# ESP32-Wrover-DevBoard.net
KiCad netlist of a schematic drawn in EAGLE
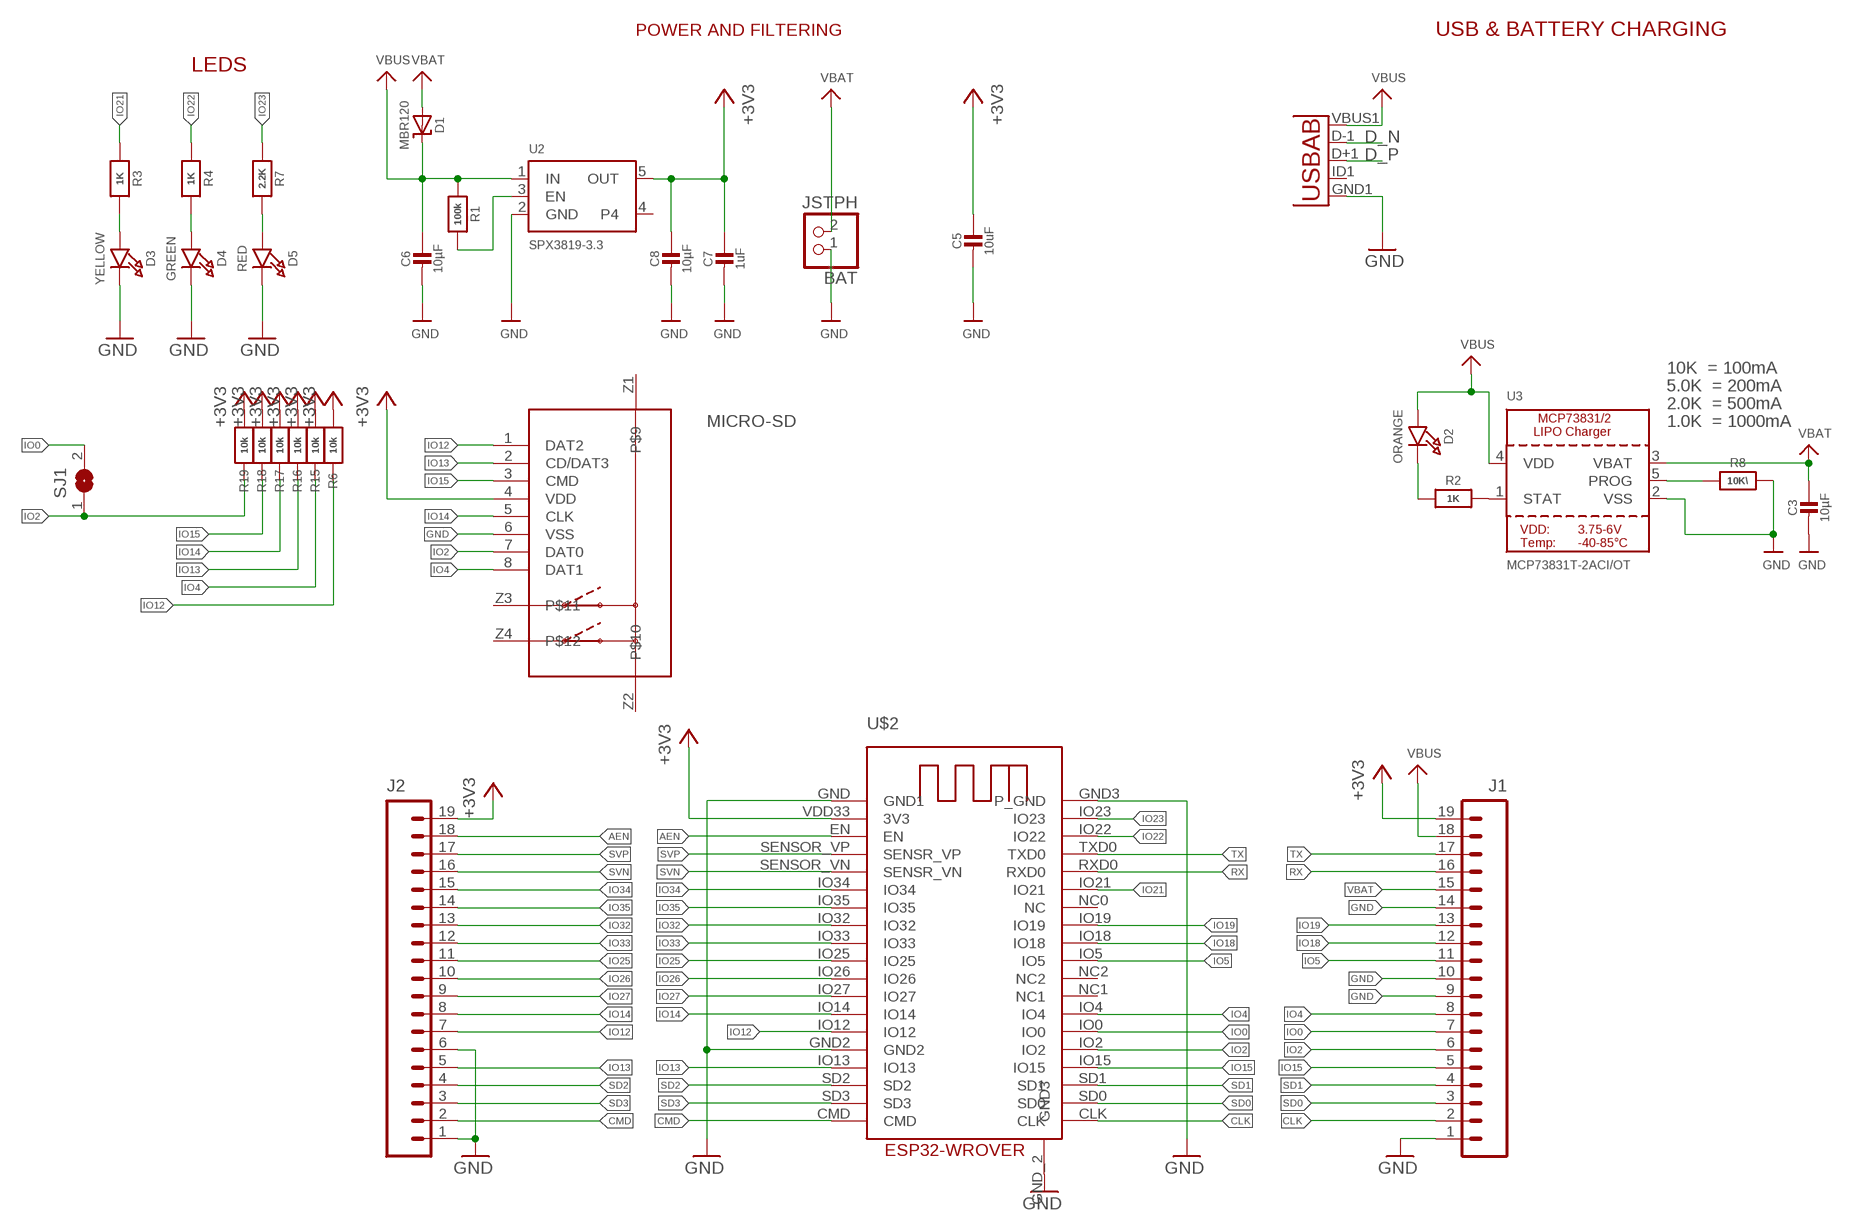
[diagram p0: schematic, sheet 1, part 1 of 2]
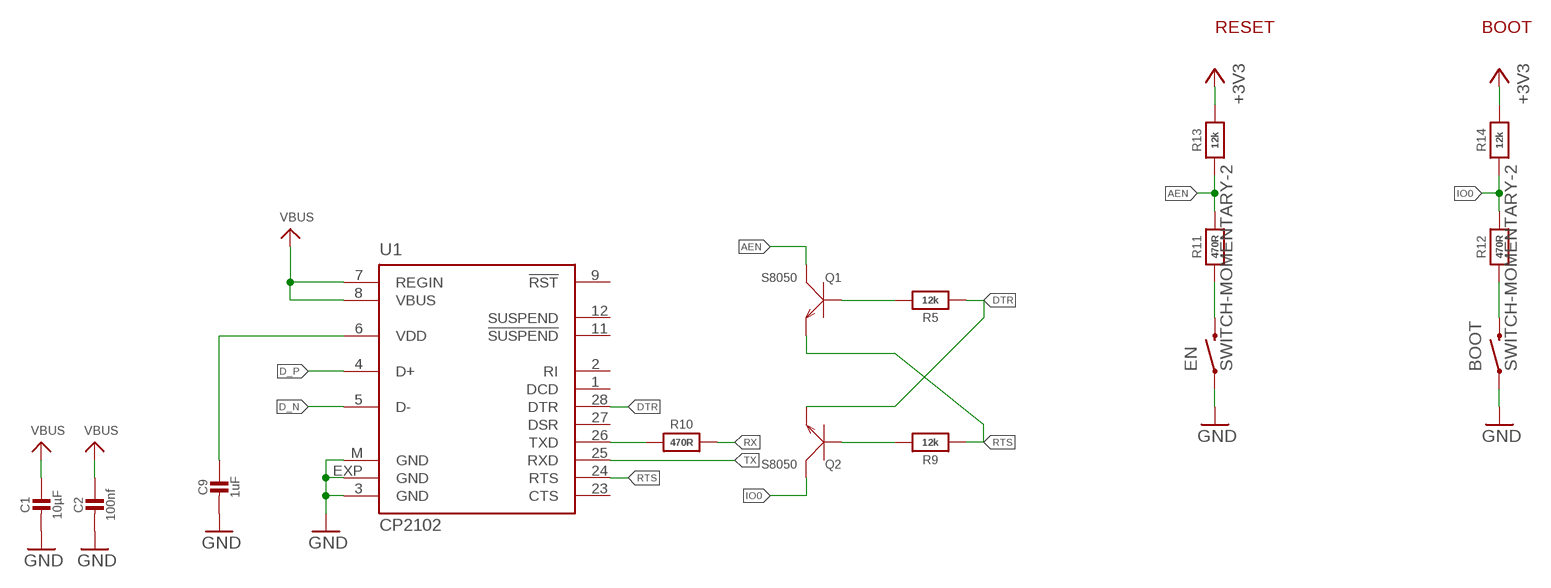
[diagram p1: schematic, sheet 1, part 2 of 2]

(export (version "E")
  (design (tool "Eeschema 10.0.6"))
  (components
    (comp (ref "BAT")
      (value "JSTPH")
      (footprint "eagle-import:JSTPH2")
      (libsource (lib "eagle-import") (part "CON_JST_PH_2PIN"))
    )
    (comp (ref "BOOT")
      (value "SWITCH-MOMENTARY-2")
      (footprint "eagle-import:WS-TRS-6.0X3.5MM-TACT-SWITCH_SMD")
      (libsource (lib "eagle-import") (part "SWITCH-MOMENTARY-2"))
    )
    (comp (ref "C1")
      (value "10µF")
      (footprint "eagle-import:0805-NO")
      (libsource (lib "eagle-import") (part "CAP_CERAMIC0805-NOOUTLINE"))
    )
    (comp (ref "C2")
      (value "100nf")
      (footprint "eagle-import:0603-NO")
      (libsource (lib "eagle-import") (part "CAP_CERAMIC0603_NO"))
    )
    (comp (ref "C3")
      (value "10µF")
      (footprint "eagle-import:0805-NO")
      (libsource (lib "eagle-import") (part "CAP_CERAMIC0805-NOOUTLINE"))
    )
    (comp (ref "C5")
      (value "10uF")
      (footprint "eagle-import:0805-NO")
      (libsource (lib "eagle-import") (part "CAP_CERAMIC0805-NOOUTLINE"))
    )
    (comp (ref "C6")
      (value "10µF")
      (footprint "eagle-import:0805-NO")
      (libsource (lib "eagle-import") (part "CAP_CERAMIC0805-NOOUTLINE"))
    )
    (comp (ref "C7")
      (value "1uF")
      (footprint "eagle-import:0603-NO")
      (libsource (lib "eagle-import") (part "CAP_CERAMIC0603_NO"))
    )
    (comp (ref "C8")
      (value "10µF")
      (footprint "eagle-import:0805-NO")
      (libsource (lib "eagle-import") (part "CAP_CERAMIC0805-NOOUTLINE"))
    )
    (comp (ref "C9")
      (value "1uF")
      (footprint "eagle-import:0603-NO")
      (libsource (lib "eagle-import") (part "CAP_CERAMIC0603_NO"))
    )
    (comp (ref "D1")
      (value "MBR120")
      (footprint "eagle-import:SOD-123")
      (libsource (lib "eagle-import") (part "DIODE-SCHOTTKYSOD-123"))
    )
    (comp (ref "D2")
      (value "ORANGE")
      (footprint "eagle-import:CHIPLED_0805_NOOUTLINE")
      (libsource (lib "eagle-import") (part "LED0805_NOOUTLINE"))
    )
    (comp (ref "D3")
      (value "YELLOW")
      (footprint "eagle-import:CHIPLED_0805_NOOUTLINE")
      (libsource (lib "eagle-import") (part "LED0805_NOOUTLINE"))
    )
    (comp (ref "D4")
      (value "GREEN")
      (footprint "eagle-import:CHIPLED_0805_NOOUTLINE")
      (libsource (lib "eagle-import") (part "LED0805_NOOUTLINE"))
    )
    (comp (ref "D5")
      (value "RED")
      (footprint "eagle-import:CHIPLED_0805_NOOUTLINE")
      (libsource (lib "eagle-import") (part "LED0805_NOOUTLINE"))
    )
    (comp (ref "EN")
      (value "SWITCH-MOMENTARY-2")
      (footprint "eagle-import:WS-TRS-6.0X3.5MM-TACT-SWITCH_SMD")
      (libsource (lib "eagle-import") (part "SWITCH-MOMENTARY-2"))
    )
    (comp (ref "J1")
      (value "M191X19_NO_SILK")
      (footprint "eagle-import:1X19_NO_SILK")
      (libsource (lib "eagle-import") (part "M191X19_NO_SILK"))
    )
    (comp (ref "J2")
      (value "M191X19_NO_SILK")
      (footprint "eagle-import:1X19_NO_SILK")
      (libsource (lib "eagle-import") (part "M191X19_NO_SILK"))
    )
    (comp (ref "M-USB")
      (value "USB\"\"")
      (footprint "eagle-import:USB-MICRO-SMD")
      (libsource (lib "eagle-import") (part "USB{dblquote}{dblquote}"))
    )
    (comp (ref "MICRO-SD")
      (value "693072010801")
      (footprint "eagle-import:693072010801")
      (libsource (lib "eagle-import") (part "693072010801"))
    )
    (comp (ref "Q1")
      (value "S8050")
      (footprint "eagle-import:SOT-23")
      (libsource (lib "eagle-import") (part "SMD-TRANSISTORS-NPN-25V-500MW-S8050(SOT-23)"))
    )
    (comp (ref "Q2")
      (value "S8050")
      (footprint "eagle-import:SOT-23")
      (libsource (lib "eagle-import") (part "SMD-TRANSISTORS-NPN-25V-500MW-S8050(SOT-23)"))
    )
    (comp (ref "R1")
      (value "100k")
      (footprint "eagle-import:0603-NO")
      (libsource (lib "eagle-import") (part "RESISTOR_0603_NOOUT"))
    )
    (comp (ref "R2")
      (value "1K")
      (footprint "eagle-import:0603-NO")
      (libsource (lib "eagle-import") (part "RESISTOR_0603_NOOUT"))
    )
    (comp (ref "R3")
      (value "1K")
      (footprint "eagle-import:0603-NO")
      (libsource (lib "eagle-import") (part "RESISTOR_0603_NOOUT"))
    )
    (comp (ref "R4")
      (value "1K")
      (footprint "eagle-import:0603-NO")
      (libsource (lib "eagle-import") (part "RESISTOR_0603_NOOUT"))
    )
    (comp (ref "R5")
      (value "12k")
      (footprint "eagle-import:0603-NO")
      (libsource (lib "eagle-import") (part "RESISTOR_0603_NOOUT"))
    )
    (comp (ref "R6")
      (value "10k")
      (footprint "eagle-import:0603-NO")
      (libsource (lib "eagle-import") (part "RESISTOR_0603_NOOUT"))
    )
    (comp (ref "R7")
      (value "2.2K")
      (footprint "eagle-import:0603-NO")
      (libsource (lib "eagle-import") (part "RESISTOR_0603_NOOUT"))
    )
    (comp (ref "R8")
      (value "10K\\")
      (footprint "eagle-import:0603-NO")
      (libsource (lib "eagle-import") (part "RESISTOR_0603_NOOUT"))
    )
    (comp (ref "R9")
      (value "12k")
      (footprint "eagle-import:0603-NO")
      (libsource (lib "eagle-import") (part "RESISTOR_0603_NOOUT"))
    )
    (comp (ref "R10")
      (value "470R")
      (footprint "eagle-import:0603-NO")
      (libsource (lib "eagle-import") (part "RESISTOR_0603_NOOUT"))
    )
    (comp (ref "R11")
      (value "470R")
      (footprint "eagle-import:0603-NO")
      (libsource (lib "eagle-import") (part "RESISTOR_0603_NOOUT"))
    )
    (comp (ref "R12")
      (value "470R")
      (footprint "eagle-import:0603-NO")
      (libsource (lib "eagle-import") (part "RESISTOR_0603_NOOUT"))
    )
    (comp (ref "R13")
      (value "12k")
      (footprint "eagle-import:0603-NO")
      (libsource (lib "eagle-import") (part "RESISTOR_0603_NOOUT"))
    )
    (comp (ref "R14")
      (value "12k")
      (footprint "eagle-import:0603-NO")
      (libsource (lib "eagle-import") (part "RESISTOR_0603_NOOUT"))
    )
    (comp (ref "R15")
      (value "10k")
      (footprint "eagle-import:0603-NO")
      (libsource (lib "eagle-import") (part "RESISTOR_0603_NOOUT"))
    )
    (comp (ref "R16")
      (value "10k")
      (footprint "eagle-import:0603-NO")
      (libsource (lib "eagle-import") (part "RESISTOR_0603_NOOUT"))
    )
    (comp (ref "R17")
      (value "10k")
      (footprint "eagle-import:0603-NO")
      (libsource (lib "eagle-import") (part "RESISTOR_0603_NOOUT"))
    )
    (comp (ref "R18")
      (value "10k")
      (footprint "eagle-import:0603-NO")
      (libsource (lib "eagle-import") (part "RESISTOR_0603_NOOUT"))
    )
    (comp (ref "R19")
      (value "10k")
      (footprint "eagle-import:0603-NO")
      (libsource (lib "eagle-import") (part "RESISTOR_0603_NOOUT"))
    )
    (comp (ref "SJ1") (value "SJ") (footprint "eagle-import:SJ") (libsource (lib "eagle-import") (part "SJ")))
    (comp (ref "U$2")
      (value "ESP32-WROVER")
      (footprint "eagle-import:ESP32-WROVER")
      (libsource (lib "eagle-import") (part "ESP32-WROVER"))
    )
    (comp (ref "U1")
      (value "CP2102")
      (footprint "eagle-import:MLP28")
      (fields (field (name "MF") "FARNELL") (field (name "MPN") "CP2102-GM"))
      (libsource (lib "eagle-import") (part "CP2102"))
    )
    (comp (ref "U2")
      (value "SPX3819-3.3")
      (footprint "eagle-import:SOT23-5")
      (libsource (lib "eagle-import") (part "VREG_SOT23-5"))
    )
    (comp (ref "U3")
      (value "MCP73831T-2ACI/OT")
      (footprint "eagle-import:SOT23-5")
      (libsource (lib "eagle-import") (part "MCP73831/2"))
    )
  )
  (nets
    (net (code "1") (name "+3V3") (class "Default")
      (node (ref "C5") (pin "1") (pinfunction "1_1") (pintype "passive"))
      (node (ref "C7") (pin "1") (pinfunction "1_1") (pintype "passive"))
      (node (ref "C8") (pin "1") (pinfunction "1_1") (pintype "passive"))
      (node (ref "J1") (pin "19") (pinfunction "19_19") (pintype "passive"))
      (node (ref "J2") (pin "19") (pinfunction "19_19") (pintype "passive"))
      (node (ref "MICRO-SD") (pin "4") (pinfunction "VDD_4") (pintype "bidirectional"))
      (node (ref "R13") (pin "2") (pinfunction "2_2") (pintype "passive"))
      (node (ref "R14") (pin "2") (pinfunction "2_2") (pintype "passive"))
      (node (ref "R15") (pin "1") (pinfunction "1_1") (pintype "passive"))
      (node (ref "R16") (pin "1") (pinfunction "1_1") (pintype "passive"))
      (node (ref "R17") (pin "1") (pinfunction "1_1") (pintype "passive"))
      (node (ref "R18") (pin "1") (pinfunction "1_1") (pintype "passive"))
      (node (ref "R19") (pin "1") (pinfunction "1_1") (pintype "passive"))
      (node (ref "R6") (pin "1") (pinfunction "1_1") (pintype "passive"))
      (node (ref "U$2") (pin "VDD33") (pinfunction "3V3_VDD33") (pintype "bidirectional"))
      (node (ref "U2") (pin "5") (pinfunction "OUT_5") (pintype "power_in"))
    )
    (net (code "2") (name "AEN") (class "Default")
      (node (ref "J2") (pin "18") (pinfunction "18_18") (pintype "passive"))
      (node (ref "Q1") (pin "3") (pinfunction "C_3") (pintype "passive"))
      (node (ref "R11") (pin "2") (pinfunction "2_2") (pintype "passive"))
      (node (ref "R13") (pin "1") (pinfunction "1_1") (pintype "passive"))
      (node (ref "U$2") (pin "EN") (pinfunction "EN_EN") (pintype "bidirectional"))
    )
    (net (code "3") (name "CLK") (class "Default")
      (node (ref "J1") (pin "2") (pinfunction "2_2") (pintype "passive"))
      (node (ref "U$2") (pin "CLK") (pinfunction "CLK_CLK") (pintype "bidirectional"))
    )
    (net (code "4") (name "CMD") (class "Default")
      (node (ref "J2") (pin "2") (pinfunction "2_2") (pintype "passive"))
      (node (ref "U$2") (pin "CMD") (pinfunction "CMD_CMD") (pintype "bidirectional"))
    )
    (net (code "5") (name "DTR") (class "Default")
      (node (ref "Q2") (pin "2") (pinfunction "E_2") (pintype "passive"))
      (node (ref "R5") (pin "1") (pinfunction "1_1") (pintype "passive"))
      (node (ref "U1") (pin "28") (pinfunction "DTR_28") (pintype "output"))
    )
    (net (code "6") (name "D_N") (class "Default")
      (node (ref "M-USB") (pin "D-1") (pinfunction "D-_D-1") (pintype "bidirectional"))
      (node (ref "U1") (pin "5") (pinfunction "D-_5") (pintype "bidirectional"))
    )
    (net (code "7") (name "D_P") (class "Default")
      (node (ref "M-USB") (pin "D+1") (pinfunction "D+_D+1") (pintype "bidirectional"))
      (node (ref "U1") (pin "4") (pinfunction "D+_4") (pintype "bidirectional"))
    )
    (net (code "8") (name "GND") (class "Default")
      (node (ref "BAT") (pin "1") (pinfunction "1_1") (pintype "passive"))
      (node (ref "BOOT") (pin "1") (pinfunction "1_1") (pintype "passive"))
      (node (ref "C1") (pin "2") (pinfunction "2_2") (pintype "passive"))
      (node (ref "C2") (pin "2") (pinfunction "2_2") (pintype "passive"))
      (node (ref "C3") (pin "2") (pinfunction "2_2") (pintype "passive"))
      (node (ref "C5") (pin "2") (pinfunction "2_2") (pintype "passive"))
      (node (ref "C6") (pin "2") (pinfunction "2_2") (pintype "passive"))
      (node (ref "C7") (pin "2") (pinfunction "2_2") (pintype "passive"))
      (node (ref "C8") (pin "2") (pinfunction "2_2") (pintype "passive"))
      (node (ref "C9") (pin "2") (pinfunction "2_2") (pintype "passive"))
      (node (ref "D3") (pin "C") (pinfunction "C_C") (pintype "passive"))
      (node (ref "D4") (pin "C") (pinfunction "C_C") (pintype "passive"))
      (node (ref "D5") (pin "C") (pinfunction "C_C") (pintype "passive"))
      (node (ref "EN") (pin "1") (pinfunction "1_1") (pintype "passive"))
      (node (ref "J1") (pin "1") (pinfunction "1_1") (pintype "passive"))
      (node (ref "J1") (pin "10") (pinfunction "10_10") (pintype "passive"))
      (node (ref "J1") (pin "14") (pinfunction "14_14") (pintype "passive"))
      (node (ref "J1") (pin "9") (pinfunction "9_9") (pintype "passive"))
      (node (ref "J2") (pin "1") (pinfunction "1_1") (pintype "passive"))
      (node (ref "J2") (pin "6") (pinfunction "6_6") (pintype "passive"))
      (node (ref "M-USB") (pin "GND1") (pinfunction "GND_GND1") (pintype "bidirectional"))
      (node (ref "MICRO-SD") (pin "6") (pinfunction "VSS_6") (pintype "bidirectional"))
      (node (ref "R8") (pin "2") (pinfunction "2_2") (pintype "passive"))
      (node (ref "U$2") (pin "GND") (pinfunction "GND1_GND") (pintype "bidirectional"))
      (node (ref "U$2") (pin "GND2") (pinfunction "GND2_GND2") (pintype "bidirectional"))
      (node (ref "U$2") (pin "GND3") (pinfunction "P_GND_GND3") (pintype "bidirectional"))
      (node (ref "U$2") (pin "GND_2") (pinfunction "GND3_GND_2") (pintype "bidirectional"))
      (node (ref "U1") (pin "3") (pinfunction "GND_3") (pintype "power_in"))
      (node (ref "U1") (pin "EXP") (pinfunction "GND_EXP") (pintype "power_in"))
      (node (ref "U1") (pin "M") (pinfunction "GND_M") (pintype "power_in"))
      (node (ref "U2") (pin "2") (pinfunction "GND_2") (pintype "power_in"))
      (node (ref "U3") (pin "2") (pinfunction "VSS_2") (pintype "power_in"))
    )
    (net (code "9") (name "IO0") (class "Default")
      (node (ref "J1") (pin "7") (pinfunction "7_7") (pintype "passive"))
      (node (ref "Q2") (pin "3") (pinfunction "C_3") (pintype "passive"))
      (node (ref "R12") (pin "2") (pinfunction "2_2") (pintype "passive"))
      (node (ref "R14") (pin "1") (pinfunction "1_1") (pintype "passive"))
      (node (ref "SJ1") (pin "2") (pinfunction "2_2") (pintype "passive"))
      (node (ref "U$2") (pin "IO0") (pinfunction "IO0_IO0") (pintype "bidirectional"))
    )
    (net (code "10") (name "IO2") (class "Default")
      (node (ref "J1") (pin "6") (pinfunction "6_6") (pintype "passive"))
      (node (ref "MICRO-SD") (pin "7") (pinfunction "DAT0_7") (pintype "bidirectional"))
      (node (ref "R19") (pin "2") (pinfunction "2_2") (pintype "passive"))
      (node (ref "SJ1") (pin "1") (pinfunction "1_1") (pintype "passive"))
      (node (ref "U$2") (pin "IO2") (pinfunction "IO2_IO2") (pintype "bidirectional"))
    )
    (net (code "11") (name "IO4") (class "Default")
      (node (ref "J1") (pin "8") (pinfunction "8_8") (pintype "passive"))
      (node (ref "MICRO-SD") (pin "8") (pinfunction "DAT1_8") (pintype "bidirectional"))
      (node (ref "R15") (pin "2") (pinfunction "2_2") (pintype "passive"))
      (node (ref "U$2") (pin "IO4") (pinfunction "IO4_IO4") (pintype "bidirectional"))
    )
    (net (code "12") (name "IO5") (class "Default")
      (node (ref "J1") (pin "11") (pinfunction "11_11") (pintype "passive"))
      (node (ref "U$2") (pin "IO5") (pinfunction "IO5_IO5") (pintype "bidirectional"))
    )
    (net (code "13") (name "IO12") (class "Default")
      (node (ref "J2") (pin "7") (pinfunction "7_7") (pintype "passive"))
      (node (ref "MICRO-SD") (pin "1") (pinfunction "DAT2_1") (pintype "bidirectional"))
      (node (ref "R6") (pin "2") (pinfunction "2_2") (pintype "passive"))
      (node (ref "U$2") (pin "IO12") (pinfunction "IO12_IO12") (pintype "bidirectional"))
    )
    (net (code "14") (name "IO13") (class "Default")
      (node (ref "J2") (pin "5") (pinfunction "5_5") (pintype "passive"))
      (node (ref "MICRO-SD") (pin "2") (pinfunction "CD/DAT3_2") (pintype "bidirectional"))
      (node (ref "R16") (pin "2") (pinfunction "2_2") (pintype "passive"))
      (node (ref "U$2") (pin "IO13") (pinfunction "IO13_IO13") (pintype "bidirectional"))
    )
    (net (code "15") (name "IO14") (class "Default")
      (node (ref "J2") (pin "8") (pinfunction "8_8") (pintype "passive"))
      (node (ref "MICRO-SD") (pin "5") (pinfunction "CLK_5") (pintype "bidirectional"))
      (node (ref "R17") (pin "2") (pinfunction "2_2") (pintype "passive"))
      (node (ref "U$2") (pin "IO14") (pinfunction "IO14_IO14") (pintype "bidirectional"))
    )
    (net (code "16") (name "IO15") (class "Default")
      (node (ref "J1") (pin "5") (pinfunction "5_5") (pintype "passive"))
      (node (ref "MICRO-SD") (pin "3") (pinfunction "CMD_3") (pintype "bidirectional"))
      (node (ref "R18") (pin "2") (pinfunction "2_2") (pintype "passive"))
      (node (ref "U$2") (pin "IO15") (pinfunction "IO15_IO15") (pintype "bidirectional"))
    )
    (net (code "17") (name "IO18") (class "Default")
      (node (ref "J1") (pin "12") (pinfunction "12_12") (pintype "passive"))
      (node (ref "U$2") (pin "IO18") (pinfunction "IO18_IO18") (pintype "bidirectional"))
    )
    (net (code "18") (name "IO19") (class "Default")
      (node (ref "J1") (pin "13") (pinfunction "13_13") (pintype "passive"))
      (node (ref "U$2") (pin "IO19") (pinfunction "IO19_IO19") (pintype "bidirectional"))
    )
    (net (code "19") (name "IO21") (class "Default")
      (node (ref "R3") (pin "1") (pinfunction "1_1") (pintype "passive"))
      (node (ref "U$2") (pin "IO21") (pinfunction "IO21_IO21") (pintype "bidirectional"))
    )
    (net (code "20") (name "IO22") (class "Default")
      (node (ref "R4") (pin "1") (pinfunction "1_1") (pintype "passive"))
      (node (ref "U$2") (pin "IO22") (pinfunction "IO22_IO22") (pintype "bidirectional"))
    )
    (net (code "21") (name "IO23") (class "Default")
      (node (ref "R7") (pin "1") (pinfunction "1_1") (pintype "passive"))
      (node (ref "U$2") (pin "IO23") (pinfunction "IO23_IO23") (pintype "bidirectional"))
    )
    (net (code "22") (name "IO25") (class "Default")
      (node (ref "J2") (pin "11") (pinfunction "11_11") (pintype "passive"))
      (node (ref "U$2") (pin "IO25") (pinfunction "IO25_IO25") (pintype "bidirectional"))
    )
    (net (code "23") (name "IO26") (class "Default")
      (node (ref "J2") (pin "10") (pinfunction "10_10") (pintype "passive"))
      (node (ref "U$2") (pin "IO26") (pinfunction "IO26_IO26") (pintype "bidirectional"))
    )
    (net (code "24") (name "IO27") (class "Default")
      (node (ref "J2") (pin "9") (pinfunction "9_9") (pintype "passive"))
      (node (ref "U$2") (pin "IO27") (pinfunction "IO27_IO27") (pintype "bidirectional"))
    )
    (net (code "25") (name "IO32") (class "Default")
      (node (ref "J2") (pin "13") (pinfunction "13_13") (pintype "passive"))
      (node (ref "U$2") (pin "IO32") (pinfunction "IO32_IO32") (pintype "bidirectional"))
    )
    (net (code "26") (name "IO33") (class "Default")
      (node (ref "J2") (pin "12") (pinfunction "12_12") (pintype "passive"))
      (node (ref "U$2") (pin "IO33") (pinfunction "IO33_IO33") (pintype "bidirectional"))
    )
    (net (code "27") (name "IO34") (class "Default")
      (node (ref "J2") (pin "15") (pinfunction "15_15") (pintype "passive"))
      (node (ref "U$2") (pin "IO34") (pinfunction "IO34_IO34") (pintype "bidirectional"))
    )
    (net (code "28") (name "IO35") (class "Default")
      (node (ref "J2") (pin "14") (pinfunction "14_14") (pintype "passive"))
      (node (ref "U$2") (pin "IO35") (pinfunction "IO35_IO35") (pintype "bidirectional"))
    )
    (net (code "29") (name "Net-(BOOT-Pad2)") (class "Default")
      (node (ref "BOOT") (pin "2") (pinfunction "2_2") (pintype "passive"))
      (node (ref "R12") (pin "1") (pinfunction "1_1") (pintype "passive"))
    )
    (net (code "30") (name "Net-(D2-PadC)") (class "Default")
      (node (ref "D2") (pin "C") (pinfunction "C_C") (pintype "passive"))
      (node (ref "R2") (pin "1") (pinfunction "1_1") (pintype "passive"))
    )
    (net (code "31") (name "Net-(D3-PadA)") (class "Default")
      (node (ref "D3") (pin "A") (pinfunction "A_A") (pintype "passive"))
      (node (ref "R3") (pin "2") (pinfunction "2_2") (pintype "passive"))
    )
    (net (code "32") (name "Net-(D4-PadA)") (class "Default")
      (node (ref "D4") (pin "A") (pinfunction "A_A") (pintype "passive"))
      (node (ref "R4") (pin "2") (pinfunction "2_2") (pintype "passive"))
    )
    (net (code "33") (name "Net-(D5-PadA)") (class "Default")
      (node (ref "D5") (pin "A") (pinfunction "A_A") (pintype "passive"))
      (node (ref "R7") (pin "2") (pinfunction "2_2") (pintype "passive"))
    )
    (net (code "34") (name "Net-(EN-Pad2)") (class "Default")
      (node (ref "EN") (pin "2") (pinfunction "2_2") (pintype "passive"))
      (node (ref "R11") (pin "1") (pinfunction "1_1") (pintype "passive"))
    )
    (net (code "35") (name "Net-(Q1-B)") (class "Default")
      (node (ref "Q1") (pin "1") (pinfunction "B_1") (pintype "passive"))
      (node (ref "R5") (pin "2") (pinfunction "2_2") (pintype "passive"))
    )
    (net (code "36") (name "Net-(Q2-B)") (class "Default")
      (node (ref "Q2") (pin "1") (pinfunction "B_1") (pintype "passive"))
      (node (ref "R9") (pin "2") (pinfunction "2_2") (pintype "passive"))
    )
    (net (code "37") (name "Net-(U1-TXD)") (class "Default")
      (node (ref "R10") (pin "1") (pinfunction "1_1") (pintype "passive"))
      (node (ref "U1") (pin "26") (pinfunction "TXD_26") (pintype "output"))
    )
    (net (code "38") (name "Net-(U1-VDD)") (class "Default")
      (node (ref "C9") (pin "1") (pinfunction "1_1") (pintype "passive"))
      (node (ref "U1") (pin "6") (pinfunction "VDD_6") (pintype "power_in"))
    )
    (net (code "39") (name "Net-(U2-EN)") (class "Default")
      (node (ref "R1") (pin "2") (pinfunction "2_2") (pintype "passive"))
      (node (ref "U2") (pin "3") (pinfunction "EN_3") (pintype "input"))
    )
    (net (code "40") (name "Net-(U3-PROG)") (class "Default")
      (node (ref "R8") (pin "1") (pinfunction "1_1") (pintype "passive"))
      (node (ref "U3") (pin "5") (pinfunction "PROG_5") (pintype "input"))
    )
    (net (code "41") (name "Net-(U3-STAT)") (class "Default")
      (node (ref "R2") (pin "2") (pinfunction "2_2") (pintype "passive"))
      (node (ref "U3") (pin "1") (pinfunction "STAT_1") (pintype "output"))
    )
    (net (code "42") (name "RTS") (class "Default")
      (node (ref "Q1") (pin "2") (pinfunction "E_2") (pintype "passive"))
      (node (ref "R9") (pin "1") (pinfunction "1_1") (pintype "passive"))
      (node (ref "U1") (pin "24") (pinfunction "RTS_24") (pintype "output"))
    )
    (net (code "43") (name "RX") (class "Default")
      (node (ref "J1") (pin "16") (pinfunction "16_16") (pintype "passive"))
      (node (ref "R10") (pin "2") (pinfunction "2_2") (pintype "passive"))
      (node (ref "U$2") (pin "RXD0") (pinfunction "RXD0_RXD0") (pintype "bidirectional"))
    )
    (net (code "44") (name "SD0") (class "Default")
      (node (ref "J1") (pin "3") (pinfunction "3_3") (pintype "passive"))
      (node (ref "U$2") (pin "SD0") (pinfunction "SD0_SD0") (pintype "bidirectional"))
    )
    (net (code "45") (name "SD1") (class "Default")
      (node (ref "J1") (pin "4") (pinfunction "4_4") (pintype "passive"))
      (node (ref "U$2") (pin "SD1") (pinfunction "SD1_SD1") (pintype "bidirectional"))
    )
    (net (code "46") (name "SD2") (class "Default")
      (node (ref "J2") (pin "4") (pinfunction "4_4") (pintype "passive"))
      (node (ref "U$2") (pin "SD2") (pinfunction "SD2_SD2") (pintype "bidirectional"))
    )
    (net (code "47") (name "SD3") (class "Default")
      (node (ref "J2") (pin "3") (pinfunction "3_3") (pintype "passive"))
      (node (ref "U$2") (pin "SD3") (pinfunction "SD3_SD3") (pintype "bidirectional"))
    )
    (net (code "48") (name "SVN") (class "Default")
      (node (ref "J2") (pin "16") (pinfunction "16_16") (pintype "passive"))
      (node (ref "U$2") (pin "SENSOR_VN") (pinfunction "SENSR_VN_SENSOR_VN") (pintype "bidirectional"))
    )
    (net (code "49") (name "SVP") (class "Default")
      (node (ref "J2") (pin "17") (pinfunction "17_17") (pintype "passive"))
      (node (ref "U$2") (pin "SENSOR_VP") (pinfunction "SENSR_VP_SENSOR_VP") (pintype "bidirectional"))
    )
    (net (code "50") (name "TX") (class "Default")
      (node (ref "J1") (pin "17") (pinfunction "17_17") (pintype "passive"))
      (node (ref "U$2") (pin "TXD0") (pinfunction "TXD0_TXD0") (pintype "bidirectional"))
      (node (ref "U1") (pin "25") (pinfunction "RXD_25") (pintype "input"))
    )
    (net (code "51") (name "VBAT") (class "Default")
      (node (ref "BAT") (pin "2") (pinfunction "2_2") (pintype "passive"))
      (node (ref "C3") (pin "1") (pinfunction "1_1") (pintype "passive"))
      (node (ref "D1") (pin "A") (pinfunction "A_A") (pintype "passive"))
      (node (ref "J1") (pin "15") (pinfunction "15_15") (pintype "passive"))
      (node (ref "U3") (pin "3") (pinfunction "VBAT_3") (pintype "power_in"))
    )
    (net (code "52") (name "VBUS") (class "Default")
      (node (ref "C1") (pin "1") (pinfunction "1_1") (pintype "passive"))
      (node (ref "C2") (pin "1") (pinfunction "1_1") (pintype "passive"))
      (node (ref "C6") (pin "1") (pinfunction "1_1") (pintype "passive"))
      (node (ref "D1") (pin "C") (pinfunction "C_C") (pintype "passive"))
      (node (ref "D2") (pin "A") (pinfunction "A_A") (pintype "passive"))
      (node (ref "J1") (pin "18") (pinfunction "18_18") (pintype "passive"))
      (node (ref "M-USB") (pin "VBUS1") (pinfunction "VBUS_VBUS1") (pintype "bidirectional"))
      (node (ref "R1") (pin "1") (pinfunction "1_1") (pintype "passive"))
      (node (ref "U1") (pin "7") (pinfunction "REGIN_7") (pintype "passive"))
      (node (ref "U1") (pin "8") (pinfunction "VBUS_8") (pintype "input"))
      (node (ref "U2") (pin "1") (pinfunction "IN_1") (pintype "power_in"))
      (node (ref "U3") (pin "4") (pinfunction "VDD_4") (pintype "power_in"))
    )
    (net (code "53") (name "unconnected-(M-USB-USBID-PadID1)") (class "Default")
      (node (ref "M-USB") (pin "ID1") (pinfunction "USBID_ID1") (pintype "bidirectional"))
    )
    (net (code "54") (name "unconnected-(MICRO-SD-P$9-PadZ1)") (class "Default")
      (node (ref "MICRO-SD") (pin "Z1") (pinfunction "P$9_Z1") (pintype "bidirectional"))
    )
    (net (code "55") (name "unconnected-(MICRO-SD-P$10-PadZ2)") (class "Default")
      (node (ref "MICRO-SD") (pin "Z2") (pinfunction "P$10_Z2") (pintype "bidirectional"))
    )
    (net (code "56") (name "unconnected-(MICRO-SD-P$11-PadZ3)") (class "Default")
      (node (ref "MICRO-SD") (pin "Z3") (pinfunction "P$11_Z3") (pintype "bidirectional"))
    )
    (net (code "57") (name "unconnected-(MICRO-SD-P$12-PadZ4)") (class "Default")
      (node (ref "MICRO-SD") (pin "Z4") (pinfunction "P$12_Z4") (pintype "bidirectional"))
    )
    (net (code "58") (name "unconnected-(U$2-NC-PadNC0)") (class "Default")
      (node (ref "U$2") (pin "NC0") (pinfunction "NC_NC0") (pintype "bidirectional"))
    )
    (net (code "59") (name "unconnected-(U$2-PadNC1)") (class "Default")
      (node (ref "U$2") (pin "NC1") (pinfunction "NC1_NC1") (pintype "bidirectional"))
    )
    (net (code "60") (name "unconnected-(U$2-PadNC2)") (class "Default")
      (node (ref "U$2") (pin "NC2") (pinfunction "NC2_NC2") (pintype "bidirectional"))
    )
    (net (code "61") (name "unconnected-(U1-CTS-Pad23)") (class "Default")
      (node (ref "U1") (pin "23") (pinfunction "CTS_23") (pintype "input"))
    )
    (net (code "62") (name "unconnected-(U1-DCD-Pad1)") (class "Default")
      (node (ref "U1") (pin "1") (pinfunction "DCD_1") (pintype "input"))
    )
    (net (code "63") (name "unconnected-(U1-DSR-Pad27)") (class "Default")
      (node (ref "U1") (pin "27") (pinfunction "DSR_27") (pintype "input"))
    )
    (net (code "64") (name "unconnected-(U1-RI-Pad2)") (class "Default")
      (node (ref "U1") (pin "2") (pinfunction "RI_2") (pintype "input"))
    )
    (net (code "65") (name "unconnected-(U1-SUSPEND-Pad12)") (class "Default")
      (node (ref "U1") (pin "12") (pinfunction "SUSPEND_12") (pintype "output"))
    )
    (net (code "66") (name "unconnected-(U1-~{RST}-Pad9)") (class "Default")
      (node (ref "U1") (pin "9") (pinfunction "~{RST}_9") (pintype "bidirectional"))
    )
    (net (code "67") (name "unconnected-(U1-~{SUSPEND}-Pad11)") (class "Default")
      (node (ref "U1") (pin "11") (pinfunction "~{SUSPEND}_11") (pintype "output"))
    )
    (net (code "68") (name "unconnected-(U2-P4-Pad4)") (class "Default")
      (node (ref "U2") (pin "4") (pinfunction "P4_4") (pintype "bidirectional"))
    )
  )
)
